# SD.net
KiCad netlist of a schematic drawn in Altium Designer
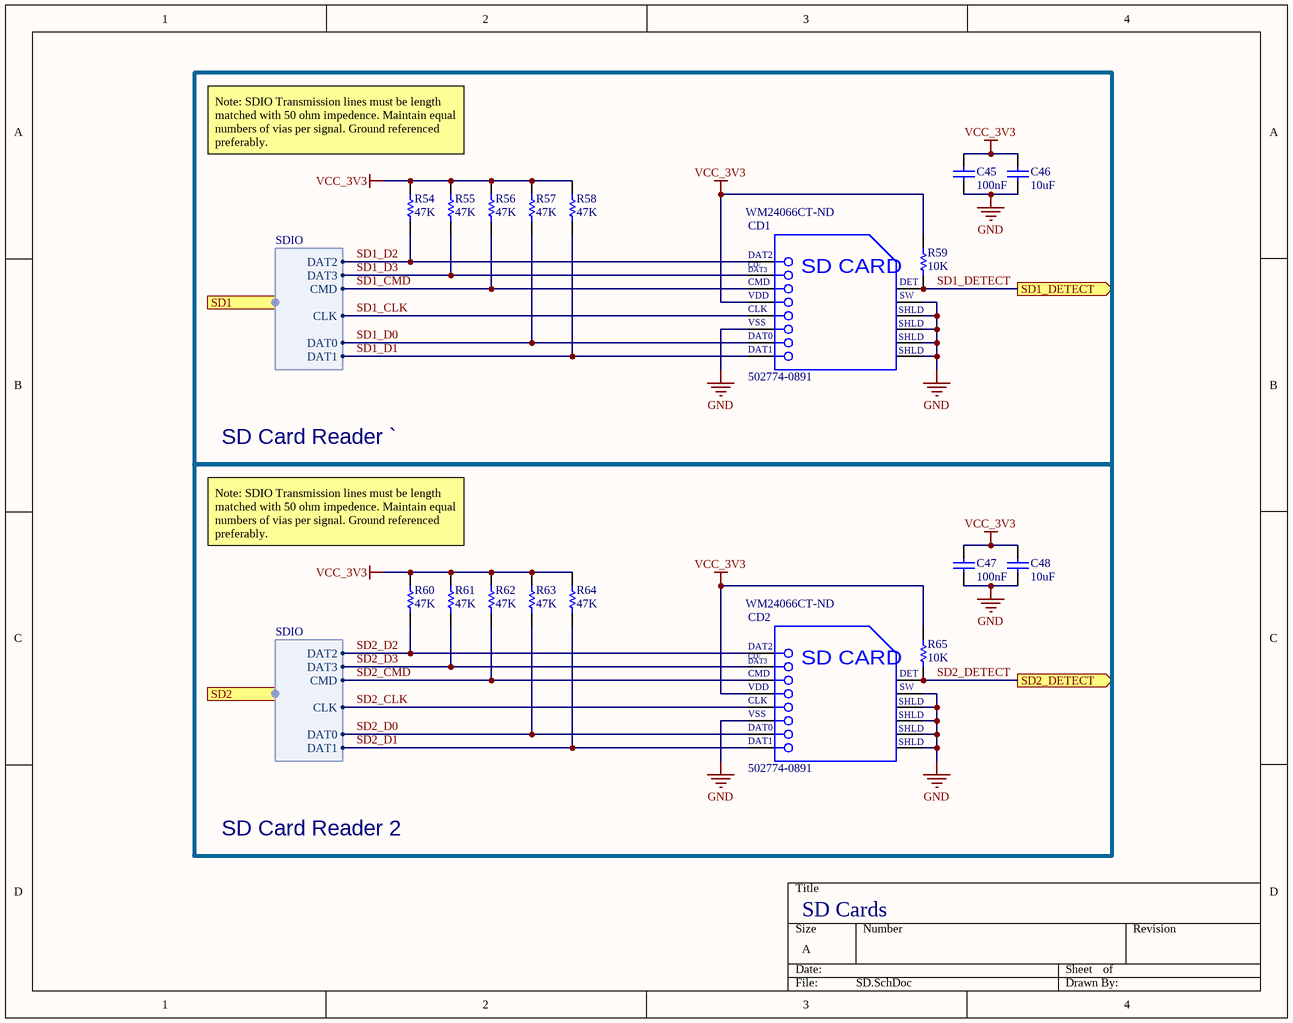
[diagram p0: SD.SchDoc]

(export (version "E")
  (design (tool "Eeschema 10.0.6"))
  (components
    (comp (ref "C45")
      (value "100nF")
      (footprint "CAPC0603(1608)100_N")
      (description "CAP 100nF 10V ±10% 0603 (1608 Metric) Thickness 1mm SMD")
      (fields (field (name "TOLERANCE") "Â±10%"))
      (libsource (lib "Altium Content Vault") (part "CMP-1035-02580-1"))
    )
    (comp (ref "C46")
      (value "10uF")
      (footprint "CAPC0603(1608)100_N")
      (description "CAP 10uF 10V ±10% 0603 (1608 Metric) Thickness 1mm SMD")
      (fields (field (name "TOLERANCE") "Â±10%"))
      (libsource (lib "Altium Content Vault") (part "CMP-1035-02799-1"))
    )
    (comp (ref "C47")
      (value "100nF")
      (footprint "CAPC0603(1608)100_N")
      (description "CAP 100nF 10V ±10% 0603 (1608 Metric) Thickness 1mm SMD")
      (fields (field (name "TOLERANCE") "Â±10%"))
      (libsource (lib "Altium Content Vault") (part "CMP-1035-02580-1"))
    )
    (comp (ref "C48")
      (value "10uF")
      (footprint "CAPC0603(1608)100_N")
      (description "CAP 10uF 10V ±10% 0603 (1608 Metric) Thickness 1mm SMD")
      (fields (field (name "TOLERANCE") "Â±10%"))
      (libsource (lib "Altium Content Vault") (part "CMP-1035-02799-1"))
    )
    (comp (ref "CD1")
      (value "502774-0891")
      (footprint "MOLX-502774-0891_V")
      (description "Micro SD Memory Card Connector, 0.5 A, 10 V (DC), -25 to 85 degC, 8-Pin SMT, RoHS, Tape and Reel")
      (fields (field (name "MANUFACTURER") "Molex") (field (name "SUPPLIER PART NUMBER 1") "WM24066CT-ND"))
      (libsource (lib "Altium Content Vault") (part "CN-SD-8-2SW-4S_B"))
    )
    (comp (ref "CD2")
      (value "502774-0891")
      (footprint "MOLX-502774-0891_V")
      (description "Micro SD Memory Card Connector, 0.5 A, 10 V (DC), -25 to 85 degC, 8-Pin SMT, RoHS, Tape and Reel")
      (fields (field (name "MANUFACTURER") "Molex") (field (name "SUPPLIER PART NUMBER 1") "WM24066CT-ND"))
      (libsource (lib "Altium Content Vault") (part "CN-SD-8-2SW-4S_B"))
    )
    (comp (ref "R54")
      (value "47K")
      (footprint "RESC0603(1608)_N")
      (description "47K 0.1W 1% 0603 (1608 Metric)  SMD")
      (fields (field (name "POWER") "0.1 W") (field (name "TOLERANCE") "1 %"))
      (libsource (lib "Altium Content Vault") (part "CMP-1012-00699-1"))
    )
    (comp (ref "R55")
      (value "47K")
      (footprint "RESC0603(1608)_N")
      (description "47K 0.1W 1% 0603 (1608 Metric)  SMD")
      (fields (field (name "POWER") "0.1 W") (field (name "TOLERANCE") "1 %"))
      (libsource (lib "Altium Content Vault") (part "CMP-1012-00699-1"))
    )
    (comp (ref "R56")
      (value "47K")
      (footprint "RESC0603(1608)_N")
      (description "47K 0.1W 1% 0603 (1608 Metric)  SMD")
      (fields (field (name "POWER") "0.1 W") (field (name "TOLERANCE") "1 %"))
      (libsource (lib "Altium Content Vault") (part "CMP-1012-00699-1"))
    )
    (comp (ref "R57")
      (value "47K")
      (footprint "RESC0603(1608)_N")
      (description "47K 0.1W 1% 0603 (1608 Metric)  SMD")
      (fields (field (name "POWER") "0.1 W") (field (name "TOLERANCE") "1 %"))
      (libsource (lib "Altium Content Vault") (part "CMP-1012-00699-1"))
    )
    (comp (ref "R58")
      (value "47K")
      (footprint "RESC0603(1608)_N")
      (description "47K 0.1W 1% 0603 (1608 Metric)  SMD")
      (fields (field (name "POWER") "0.1 W") (field (name "TOLERANCE") "1 %"))
      (libsource (lib "Altium Content Vault") (part "CMP-1012-00699-1"))
    )
    (comp (ref "R59")
      (value "10K")
      (footprint "RESC0603(1608)_N")
      (description "10K 0.1W 5% 0603 (1608 Metric)  SMD")
      (fields (field (name "TOLERANCE") "5 %") (field (name "POWER") "0.1 W"))
      (libsource (lib "Altium Content Vault") (part "CMP-1012-00098-1"))
    )
    (comp (ref "R60")
      (value "47K")
      (footprint "RESC0603(1608)_N")
      (description "47K 0.1W 1% 0603 (1608 Metric)  SMD")
      (fields (field (name "POWER") "0.1 W") (field (name "TOLERANCE") "1 %"))
      (libsource (lib "Altium Content Vault") (part "CMP-1012-00699-1"))
    )
    (comp (ref "R61")
      (value "47K")
      (footprint "RESC0603(1608)_N")
      (description "47K 0.1W 1% 0603 (1608 Metric)  SMD")
      (fields (field (name "POWER") "0.1 W") (field (name "TOLERANCE") "1 %"))
      (libsource (lib "Altium Content Vault") (part "CMP-1012-00699-1"))
    )
    (comp (ref "R62")
      (value "47K")
      (footprint "RESC0603(1608)_N")
      (description "47K 0.1W 1% 0603 (1608 Metric)  SMD")
      (fields (field (name "POWER") "0.1 W") (field (name "TOLERANCE") "1 %"))
      (libsource (lib "Altium Content Vault") (part "CMP-1012-00699-1"))
    )
    (comp (ref "R63")
      (value "47K")
      (footprint "RESC0603(1608)_N")
      (description "47K 0.1W 1% 0603 (1608 Metric)  SMD")
      (fields (field (name "POWER") "0.1 W") (field (name "TOLERANCE") "1 %"))
      (libsource (lib "Altium Content Vault") (part "CMP-1012-00699-1"))
    )
    (comp (ref "R64")
      (value "47K")
      (footprint "RESC0603(1608)_N")
      (description "47K 0.1W 1% 0603 (1608 Metric)  SMD")
      (fields (field (name "POWER") "0.1 W") (field (name "TOLERANCE") "1 %"))
      (libsource (lib "Altium Content Vault") (part "CMP-1012-00699-1"))
    )
    (comp (ref "R65")
      (value "10K")
      (footprint "RESC0603(1608)_N")
      (description "10K 0.1W 5% 0603 (1608 Metric)  SMD")
      (fields (field (name "TOLERANCE") "5 %") (field (name "POWER") "0.1 W"))
      (libsource (lib "Altium Content Vault") (part "CMP-1012-00098-1"))
    )
  )
  (nets
    (net (code "2") (name "/SD1_CLK") (class "Default")
      (node (ref "CD1") (pin "5") (pinfunction "CLK_5") (pintype "passive"))
    )
    (net (code "3") (name "/SD1_CMD") (class "Default")
      (node (ref "CD1") (pin "3") (pinfunction "CMD_3") (pintype "passive"))
      (node (ref "R56") (pin "1") (pinfunction "1_1") (pintype "passive"))
    )
    (net (code "4") (name "/SD1_D0") (class "Default")
      (node (ref "CD1") (pin "7") (pinfunction "DAT0_7") (pintype "passive"))
      (node (ref "R57") (pin "1") (pinfunction "1_1") (pintype "passive"))
    )
    (net (code "5") (name "/SD1_D1") (class "Default")
      (node (ref "CD1") (pin "8") (pinfunction "DAT1_8") (pintype "passive"))
      (node (ref "R58") (pin "1") (pinfunction "1_1") (pintype "passive"))
    )
    (net (code "6") (name "/SD1_D2") (class "Default")
      (node (ref "CD1") (pin "1") (pinfunction "DAT2_1") (pintype "passive"))
      (node (ref "R54") (pin "1") (pinfunction "1_1") (pintype "passive"))
    )
    (net (code "7") (name "/SD1_D3") (class "Default")
      (node (ref "CD1") (pin "2") (pinfunction "CD/DAT3_2") (pintype "passive"))
      (node (ref "R55") (pin "1") (pinfunction "1_1") (pintype "passive"))
    )
    (net (code "8") (name "/SD1_DETECT") (class "Default")
      (node (ref "CD1") (pin "9") (pinfunction "DETECT_9") (pintype "passive"))
      (node (ref "R59") (pin "1") (pinfunction "1_1") (pintype "passive"))
    )
    (net (code "9") (name "/SD2_CLK") (class "Default")
      (node (ref "CD2") (pin "5") (pinfunction "CLK_5") (pintype "passive"))
    )
    (net (code "10") (name "/SD2_CMD") (class "Default")
      (node (ref "CD2") (pin "3") (pinfunction "CMD_3") (pintype "passive"))
      (node (ref "R62") (pin "1") (pinfunction "1_1") (pintype "passive"))
    )
    (net (code "11") (name "/SD2_D0") (class "Default")
      (node (ref "CD2") (pin "7") (pinfunction "DAT0_7") (pintype "passive"))
      (node (ref "R63") (pin "1") (pinfunction "1_1") (pintype "passive"))
    )
    (net (code "12") (name "/SD2_D1") (class "Default")
      (node (ref "CD2") (pin "8") (pinfunction "DAT1_8") (pintype "passive"))
      (node (ref "R64") (pin "1") (pinfunction "1_1") (pintype "passive"))
    )
    (net (code "13") (name "/SD2_D2") (class "Default")
      (node (ref "CD2") (pin "1") (pinfunction "DAT2_1") (pintype "passive"))
      (node (ref "R60") (pin "1") (pinfunction "1_1") (pintype "passive"))
    )
    (net (code "14") (name "/SD2_D3") (class "Default")
      (node (ref "CD2") (pin "2") (pinfunction "CD/DAT3_2") (pintype "passive"))
      (node (ref "R61") (pin "1") (pinfunction "1_1") (pintype "passive"))
    )
    (net (code "15") (name "/SD2_DETECT") (class "Default")
      (node (ref "CD2") (pin "9") (pinfunction "DETECT_9") (pintype "passive"))
      (node (ref "R65") (pin "1") (pinfunction "1_1") (pintype "passive"))
    )
    (net (code "17") (name "GND") (class "Default")
      (node (ref "C45") (pin "1") (pinfunction "1_1") (pintype "passive"))
      (node (ref "C46") (pin "1") (pinfunction "1_1") (pintype "passive"))
      (node (ref "C47") (pin "1") (pinfunction "1_1") (pintype "passive"))
      (node (ref "C48") (pin "1") (pinfunction "1_1") (pintype "passive"))
      (node (ref "CD1") (pin "10") (pinfunction "SWITCH_10") (pintype "passive"))
      (node (ref "CD1") (pin "11") (pinfunction "SHLD_11") (pintype "passive"))
      (node (ref "CD1") (pin "12") (pinfunction "SHLD_12") (pintype "passive"))
      (node (ref "CD1") (pin "13") (pinfunction "SHLD_13") (pintype "passive"))
      (node (ref "CD1") (pin "14") (pinfunction "SHLD_14") (pintype "passive"))
      (node (ref "CD1") (pin "6") (pinfunction "VSS_6") (pintype "passive"))
      (node (ref "CD2") (pin "10") (pinfunction "SWITCH_10") (pintype "passive"))
      (node (ref "CD2") (pin "11") (pinfunction "SHLD_11") (pintype "passive"))
      (node (ref "CD2") (pin "12") (pinfunction "SHLD_12") (pintype "passive"))
      (node (ref "CD2") (pin "13") (pinfunction "SHLD_13") (pintype "passive"))
      (node (ref "CD2") (pin "14") (pinfunction "SHLD_14") (pintype "passive"))
      (node (ref "CD2") (pin "6") (pinfunction "VSS_6") (pintype "passive"))
    )
    (net (code "18") (name "VCC_3V3") (class "Default")
      (node (ref "C45") (pin "2") (pinfunction "2_2") (pintype "passive"))
      (node (ref "C46") (pin "2") (pinfunction "2_2") (pintype "passive"))
      (node (ref "C47") (pin "2") (pinfunction "2_2") (pintype "passive"))
      (node (ref "C48") (pin "2") (pinfunction "2_2") (pintype "passive"))
      (node (ref "CD1") (pin "4") (pinfunction "VDD_4") (pintype "passive"))
      (node (ref "CD2") (pin "4") (pinfunction "VDD_4") (pintype "passive"))
      (node (ref "R54") (pin "2") (pinfunction "2_2") (pintype "passive"))
      (node (ref "R55") (pin "2") (pinfunction "2_2") (pintype "passive"))
      (node (ref "R56") (pin "2") (pinfunction "2_2") (pintype "passive"))
      (node (ref "R57") (pin "2") (pinfunction "2_2") (pintype "passive"))
      (node (ref "R58") (pin "2") (pinfunction "2_2") (pintype "passive"))
      (node (ref "R59") (pin "2") (pinfunction "2_2") (pintype "passive"))
      (node (ref "R60") (pin "2") (pinfunction "2_2") (pintype "passive"))
      (node (ref "R61") (pin "2") (pinfunction "2_2") (pintype "passive"))
      (node (ref "R62") (pin "2") (pinfunction "2_2") (pintype "passive"))
      (node (ref "R63") (pin "2") (pinfunction "2_2") (pintype "passive"))
      (node (ref "R64") (pin "2") (pinfunction "2_2") (pintype "passive"))
      (node (ref "R65") (pin "2") (pinfunction "2_2") (pintype "passive"))
    )
  )
)
